# schematic.net
KiCad netlist of a schematic drawn in EAGLE
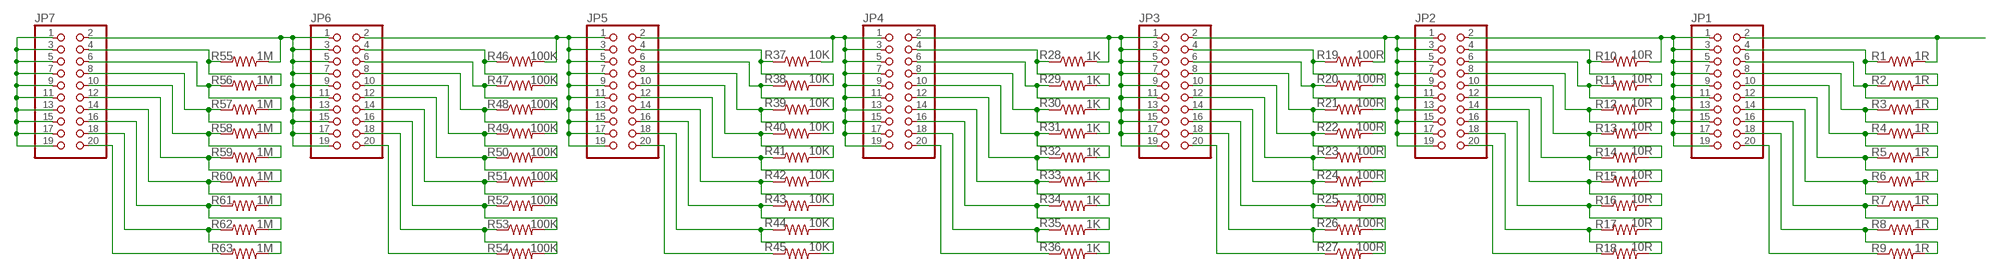
[diagram p0: schematic, sheet 1]

(export (version "E")
  (design (tool "Eeschema 10.0.6"))
  (components
    (comp (ref "JP1")
      (value "PINHD-2X10_2.54-SMD")
      (footprint "eagle-import:2X10SMD")
      (libsource (lib "eagle-import") (part "PINHD-2X10_2.54-SMD"))
    )
    (comp (ref "JP2")
      (value "PINHD-2X10_2.54-SMD")
      (footprint "eagle-import:2X10SMD")
      (libsource (lib "eagle-import") (part "PINHD-2X10_2.54-SMD"))
    )
    (comp (ref "JP3")
      (value "PINHD-2X10_2.54-SMD")
      (footprint "eagle-import:2X10SMD")
      (libsource (lib "eagle-import") (part "PINHD-2X10_2.54-SMD"))
    )
    (comp (ref "JP4")
      (value "PINHD-2X10_2.54-SMD")
      (footprint "eagle-import:2X10SMD")
      (libsource (lib "eagle-import") (part "PINHD-2X10_2.54-SMD"))
    )
    (comp (ref "JP5")
      (value "PINHD-2X10_2.54-SMD")
      (footprint "eagle-import:2X10SMD")
      (libsource (lib "eagle-import") (part "PINHD-2X10_2.54-SMD"))
    )
    (comp (ref "JP6")
      (value "PINHD-2X10_2.54-SMD")
      (footprint "eagle-import:2X10SMD")
      (libsource (lib "eagle-import") (part "PINHD-2X10_2.54-SMD"))
    )
    (comp (ref "JP7")
      (value "PINHD-2X10_2.54-SMD")
      (footprint "eagle-import:2X10SMD")
      (libsource (lib "eagle-import") (part "PINHD-2X10_2.54-SMD"))
    )
    (comp (ref "R1")
      (value "1R")
      (footprint "eagle-import:1206")
      (libsource (lib "eagle-import") (part "RESISTOR1206"))
    )
    (comp (ref "R2")
      (value "1R")
      (footprint "eagle-import:1206")
      (libsource (lib "eagle-import") (part "RESISTOR1206"))
    )
    (comp (ref "R3")
      (value "1R")
      (footprint "eagle-import:1206")
      (libsource (lib "eagle-import") (part "RESISTOR1206"))
    )
    (comp (ref "R4")
      (value "1R")
      (footprint "eagle-import:1206")
      (libsource (lib "eagle-import") (part "RESISTOR1206"))
    )
    (comp (ref "R5")
      (value "1R")
      (footprint "eagle-import:1206")
      (libsource (lib "eagle-import") (part "RESISTOR1206"))
    )
    (comp (ref "R6")
      (value "1R")
      (footprint "eagle-import:1206")
      (libsource (lib "eagle-import") (part "RESISTOR1206"))
    )
    (comp (ref "R7")
      (value "1R")
      (footprint "eagle-import:1206")
      (libsource (lib "eagle-import") (part "RESISTOR1206"))
    )
    (comp (ref "R8")
      (value "1R")
      (footprint "eagle-import:1206")
      (libsource (lib "eagle-import") (part "RESISTOR1206"))
    )
    (comp (ref "R9")
      (value "1R")
      (footprint "eagle-import:1206")
      (libsource (lib "eagle-import") (part "RESISTOR1206"))
    )
    (comp (ref "R10")
      (value "10R")
      (footprint "eagle-import:R2512")
      (libsource (lib "eagle-import") (part "RESISTOR2512"))
    )
    (comp (ref "R11")
      (value "10R")
      (footprint "eagle-import:R2512")
      (libsource (lib "eagle-import") (part "RESISTOR2512"))
    )
    (comp (ref "R12")
      (value "10R")
      (footprint "eagle-import:R2512")
      (libsource (lib "eagle-import") (part "RESISTOR2512"))
    )
    (comp (ref "R13")
      (value "10R")
      (footprint "eagle-import:R2512")
      (libsource (lib "eagle-import") (part "RESISTOR2512"))
    )
    (comp (ref "R14")
      (value "10R")
      (footprint "eagle-import:R2512")
      (libsource (lib "eagle-import") (part "RESISTOR2512"))
    )
    (comp (ref "R15")
      (value "10R")
      (footprint "eagle-import:R2512")
      (libsource (lib "eagle-import") (part "RESISTOR2512"))
    )
    (comp (ref "R16")
      (value "10R")
      (footprint "eagle-import:R2512")
      (libsource (lib "eagle-import") (part "RESISTOR2512"))
    )
    (comp (ref "R17")
      (value "10R")
      (footprint "eagle-import:R2512")
      (libsource (lib "eagle-import") (part "RESISTOR2512"))
    )
    (comp (ref "R18")
      (value "10R")
      (footprint "eagle-import:R2512")
      (libsource (lib "eagle-import") (part "RESISTOR2512"))
    )
    (comp (ref "R19")
      (value "100R")
      (footprint "eagle-import:R2512")
      (libsource (lib "eagle-import") (part "RESISTOR2512"))
    )
    (comp (ref "R20")
      (value "100R")
      (footprint "eagle-import:R2512")
      (libsource (lib "eagle-import") (part "RESISTOR2512"))
    )
    (comp (ref "R21")
      (value "100R")
      (footprint "eagle-import:R2512")
      (libsource (lib "eagle-import") (part "RESISTOR2512"))
    )
    (comp (ref "R22")
      (value "100R")
      (footprint "eagle-import:R2512")
      (libsource (lib "eagle-import") (part "RESISTOR2512"))
    )
    (comp (ref "R23")
      (value "100R")
      (footprint "eagle-import:R2512")
      (libsource (lib "eagle-import") (part "RESISTOR2512"))
    )
    (comp (ref "R24")
      (value "100R")
      (footprint "eagle-import:R2512")
      (libsource (lib "eagle-import") (part "RESISTOR2512"))
    )
    (comp (ref "R25")
      (value "100R")
      (footprint "eagle-import:R2512")
      (libsource (lib "eagle-import") (part "RESISTOR2512"))
    )
    (comp (ref "R26")
      (value "100R")
      (footprint "eagle-import:R2512")
      (libsource (lib "eagle-import") (part "RESISTOR2512"))
    )
    (comp (ref "R27")
      (value "100R")
      (footprint "eagle-import:R2512")
      (libsource (lib "eagle-import") (part "RESISTOR2512"))
    )
    (comp (ref "R28")
      (value "1K")
      (footprint "eagle-import:R2512")
      (libsource (lib "eagle-import") (part "RESISTOR2512"))
    )
    (comp (ref "R29")
      (value "1K")
      (footprint "eagle-import:R2512")
      (libsource (lib "eagle-import") (part "RESISTOR2512"))
    )
    (comp (ref "R30")
      (value "1K")
      (footprint "eagle-import:R2512")
      (libsource (lib "eagle-import") (part "RESISTOR2512"))
    )
    (comp (ref "R31")
      (value "1K")
      (footprint "eagle-import:R2512")
      (libsource (lib "eagle-import") (part "RESISTOR2512"))
    )
    (comp (ref "R32")
      (value "1K")
      (footprint "eagle-import:R2512")
      (libsource (lib "eagle-import") (part "RESISTOR2512"))
    )
    (comp (ref "R33")
      (value "1K")
      (footprint "eagle-import:R2512")
      (libsource (lib "eagle-import") (part "RESISTOR2512"))
    )
    (comp (ref "R34")
      (value "1K")
      (footprint "eagle-import:R2512")
      (libsource (lib "eagle-import") (part "RESISTOR2512"))
    )
    (comp (ref "R35")
      (value "1K")
      (footprint "eagle-import:R2512")
      (libsource (lib "eagle-import") (part "RESISTOR2512"))
    )
    (comp (ref "R36")
      (value "1K")
      (footprint "eagle-import:R2512")
      (libsource (lib "eagle-import") (part "RESISTOR2512"))
    )
    (comp (ref "R37")
      (value "10K")
      (footprint "eagle-import:R2512")
      (libsource (lib "eagle-import") (part "RESISTOR2512"))
    )
    (comp (ref "R38")
      (value "10K")
      (footprint "eagle-import:R2512")
      (libsource (lib "eagle-import") (part "RESISTOR2512"))
    )
    (comp (ref "R39")
      (value "10K")
      (footprint "eagle-import:R2512")
      (libsource (lib "eagle-import") (part "RESISTOR2512"))
    )
    (comp (ref "R40")
      (value "10K")
      (footprint "eagle-import:R2512")
      (libsource (lib "eagle-import") (part "RESISTOR2512"))
    )
    (comp (ref "R41")
      (value "10K")
      (footprint "eagle-import:R2512")
      (libsource (lib "eagle-import") (part "RESISTOR2512"))
    )
    (comp (ref "R42")
      (value "10K")
      (footprint "eagle-import:R2512")
      (libsource (lib "eagle-import") (part "RESISTOR2512"))
    )
    (comp (ref "R43")
      (value "10K")
      (footprint "eagle-import:R2512")
      (libsource (lib "eagle-import") (part "RESISTOR2512"))
    )
    (comp (ref "R44")
      (value "10K")
      (footprint "eagle-import:R2512")
      (libsource (lib "eagle-import") (part "RESISTOR2512"))
    )
    (comp (ref "R45")
      (value "10K")
      (footprint "eagle-import:R2512")
      (libsource (lib "eagle-import") (part "RESISTOR2512"))
    )
    (comp (ref "R46")
      (value "100K")
      (footprint "eagle-import:R2512")
      (libsource (lib "eagle-import") (part "RESISTOR2512"))
    )
    (comp (ref "R47")
      (value "100K")
      (footprint "eagle-import:R2512")
      (libsource (lib "eagle-import") (part "RESISTOR2512"))
    )
    (comp (ref "R48")
      (value "100K")
      (footprint "eagle-import:R2512")
      (libsource (lib "eagle-import") (part "RESISTOR2512"))
    )
    (comp (ref "R49")
      (value "100K")
      (footprint "eagle-import:R2512")
      (libsource (lib "eagle-import") (part "RESISTOR2512"))
    )
    (comp (ref "R50")
      (value "100K")
      (footprint "eagle-import:R2512")
      (libsource (lib "eagle-import") (part "RESISTOR2512"))
    )
    (comp (ref "R51")
      (value "100K")
      (footprint "eagle-import:R2512")
      (libsource (lib "eagle-import") (part "RESISTOR2512"))
    )
    (comp (ref "R52")
      (value "100K")
      (footprint "eagle-import:R2512")
      (libsource (lib "eagle-import") (part "RESISTOR2512"))
    )
    (comp (ref "R53")
      (value "100K")
      (footprint "eagle-import:R2512")
      (libsource (lib "eagle-import") (part "RESISTOR2512"))
    )
    (comp (ref "R54")
      (value "100K")
      (footprint "eagle-import:R2512")
      (libsource (lib "eagle-import") (part "RESISTOR2512"))
    )
    (comp (ref "R55")
      (value "1M")
      (footprint "eagle-import:R2512")
      (libsource (lib "eagle-import") (part "RESISTOR2512"))
    )
    (comp (ref "R56")
      (value "1M")
      (footprint "eagle-import:R2512")
      (libsource (lib "eagle-import") (part "RESISTOR2512"))
    )
    (comp (ref "R57")
      (value "1M")
      (footprint "eagle-import:R2512")
      (libsource (lib "eagle-import") (part "RESISTOR2512"))
    )
    (comp (ref "R58")
      (value "1M")
      (footprint "eagle-import:R2512")
      (libsource (lib "eagle-import") (part "RESISTOR2512"))
    )
    (comp (ref "R59")
      (value "1M")
      (footprint "eagle-import:R2512")
      (libsource (lib "eagle-import") (part "RESISTOR2512"))
    )
    (comp (ref "R60")
      (value "1M")
      (footprint "eagle-import:R2512")
      (libsource (lib "eagle-import") (part "RESISTOR2512"))
    )
    (comp (ref "R61")
      (value "1M")
      (footprint "eagle-import:R2512")
      (libsource (lib "eagle-import") (part "RESISTOR2512"))
    )
    (comp (ref "R62")
      (value "1M")
      (footprint "eagle-import:R2512")
      (libsource (lib "eagle-import") (part "RESISTOR2512"))
    )
    (comp (ref "R63")
      (value "1M")
      (footprint "eagle-import:R2512")
      (libsource (lib "eagle-import") (part "RESISTOR2512"))
    )
  )
  (nets
    (net (code "1") (name "Net-(JP1-Pad1)") (class "Default")
      (node (ref "JP1") (pin "1") (pinfunction "1_1") (pintype "passive"))
      (node (ref "JP1") (pin "11") (pinfunction "11_11") (pintype "passive"))
      (node (ref "JP1") (pin "13") (pinfunction "13_13") (pintype "passive"))
      (node (ref "JP1") (pin "15") (pinfunction "15_15") (pintype "passive"))
      (node (ref "JP1") (pin "17") (pinfunction "17_17") (pintype "passive"))
      (node (ref "JP1") (pin "19") (pinfunction "19_19") (pintype "passive"))
      (node (ref "JP1") (pin "3") (pinfunction "3_3") (pintype "passive"))
      (node (ref "JP1") (pin "5") (pinfunction "5_5") (pintype "passive"))
      (node (ref "JP1") (pin "7") (pinfunction "7_7") (pintype "passive"))
      (node (ref "JP1") (pin "9") (pinfunction "9_9") (pintype "passive"))
      (node (ref "JP2") (pin "2") (pinfunction "2_2") (pintype "passive"))
      (node (ref "R10") (pin "2") (pinfunction "2_2") (pintype "passive"))
    )
    (net (code "2") (name "Net-(JP1-Pad2)") (class "Default")
      (node (ref "JP1") (pin "2") (pinfunction "2_2") (pintype "passive"))
      (node (ref "R1") (pin "2") (pinfunction "2_2") (pintype "passive"))
    )
    (net (code "3") (name "Net-(JP1-Pad4)") (class "Default")
      (node (ref "JP1") (pin "4") (pinfunction "4_4") (pintype "passive"))
      (node (ref "R1") (pin "1") (pinfunction "1_1") (pintype "passive"))
      (node (ref "R2") (pin "2") (pinfunction "2_2") (pintype "passive"))
    )
    (net (code "4") (name "Net-(JP1-Pad6)") (class "Default")
      (node (ref "JP1") (pin "6") (pinfunction "6_6") (pintype "passive"))
      (node (ref "R2") (pin "1") (pinfunction "1_1") (pintype "passive"))
      (node (ref "R3") (pin "2") (pinfunction "2_2") (pintype "passive"))
    )
    (net (code "5") (name "Net-(JP1-Pad8)") (class "Default")
      (node (ref "JP1") (pin "8") (pinfunction "8_8") (pintype "passive"))
      (node (ref "R3") (pin "1") (pinfunction "1_1") (pintype "passive"))
      (node (ref "R4") (pin "2") (pinfunction "2_2") (pintype "passive"))
    )
    (net (code "6") (name "Net-(JP1-Pad10)") (class "Default")
      (node (ref "JP1") (pin "10") (pinfunction "10_10") (pintype "passive"))
      (node (ref "R4") (pin "1") (pinfunction "1_1") (pintype "passive"))
      (node (ref "R5") (pin "2") (pinfunction "2_2") (pintype "passive"))
    )
    (net (code "7") (name "Net-(JP1-Pad12)") (class "Default")
      (node (ref "JP1") (pin "12") (pinfunction "12_12") (pintype "passive"))
      (node (ref "R5") (pin "1") (pinfunction "1_1") (pintype "passive"))
      (node (ref "R6") (pin "2") (pinfunction "2_2") (pintype "passive"))
    )
    (net (code "8") (name "Net-(JP1-Pad14)") (class "Default")
      (node (ref "JP1") (pin "14") (pinfunction "14_14") (pintype "passive"))
      (node (ref "R6") (pin "1") (pinfunction "1_1") (pintype "passive"))
      (node (ref "R7") (pin "2") (pinfunction "2_2") (pintype "passive"))
    )
    (net (code "9") (name "Net-(JP1-Pad16)") (class "Default")
      (node (ref "JP1") (pin "16") (pinfunction "16_16") (pintype "passive"))
      (node (ref "R7") (pin "1") (pinfunction "1_1") (pintype "passive"))
      (node (ref "R8") (pin "2") (pinfunction "2_2") (pintype "passive"))
    )
    (net (code "10") (name "Net-(JP1-Pad18)") (class "Default")
      (node (ref "JP1") (pin "18") (pinfunction "18_18") (pintype "passive"))
      (node (ref "R8") (pin "1") (pinfunction "1_1") (pintype "passive"))
      (node (ref "R9") (pin "2") (pinfunction "2_2") (pintype "passive"))
    )
    (net (code "11") (name "Net-(JP1-Pad20)") (class "Default")
      (node (ref "JP1") (pin "20") (pinfunction "20_20") (pintype "passive"))
      (node (ref "R9") (pin "1") (pinfunction "1_1") (pintype "passive"))
    )
    (net (code "12") (name "Net-(JP2-Pad1)") (class "Default")
      (node (ref "JP2") (pin "1") (pinfunction "1_1") (pintype "passive"))
      (node (ref "JP2") (pin "11") (pinfunction "11_11") (pintype "passive"))
      (node (ref "JP2") (pin "13") (pinfunction "13_13") (pintype "passive"))
      (node (ref "JP2") (pin "15") (pinfunction "15_15") (pintype "passive"))
      (node (ref "JP2") (pin "17") (pinfunction "17_17") (pintype "passive"))
      (node (ref "JP2") (pin "19") (pinfunction "19_19") (pintype "passive"))
      (node (ref "JP2") (pin "3") (pinfunction "3_3") (pintype "passive"))
      (node (ref "JP2") (pin "5") (pinfunction "5_5") (pintype "passive"))
      (node (ref "JP2") (pin "7") (pinfunction "7_7") (pintype "passive"))
      (node (ref "JP2") (pin "9") (pinfunction "9_9") (pintype "passive"))
      (node (ref "JP3") (pin "2") (pinfunction "2_2") (pintype "passive"))
      (node (ref "R19") (pin "2") (pinfunction "2_2") (pintype "passive"))
    )
    (net (code "13") (name "Net-(JP2-Pad4)") (class "Default")
      (node (ref "JP2") (pin "4") (pinfunction "4_4") (pintype "passive"))
      (node (ref "R10") (pin "1") (pinfunction "1_1") (pintype "passive"))
      (node (ref "R11") (pin "2") (pinfunction "2_2") (pintype "passive"))
    )
    (net (code "14") (name "Net-(JP2-Pad6)") (class "Default")
      (node (ref "JP2") (pin "6") (pinfunction "6_6") (pintype "passive"))
      (node (ref "R11") (pin "1") (pinfunction "1_1") (pintype "passive"))
      (node (ref "R12") (pin "2") (pinfunction "2_2") (pintype "passive"))
    )
    (net (code "15") (name "Net-(JP2-Pad8)") (class "Default")
      (node (ref "JP2") (pin "8") (pinfunction "8_8") (pintype "passive"))
      (node (ref "R12") (pin "1") (pinfunction "1_1") (pintype "passive"))
      (node (ref "R13") (pin "2") (pinfunction "2_2") (pintype "passive"))
    )
    (net (code "16") (name "Net-(JP2-Pad10)") (class "Default")
      (node (ref "JP2") (pin "10") (pinfunction "10_10") (pintype "passive"))
      (node (ref "R13") (pin "1") (pinfunction "1_1") (pintype "passive"))
      (node (ref "R14") (pin "2") (pinfunction "2_2") (pintype "passive"))
    )
    (net (code "17") (name "Net-(JP2-Pad12)") (class "Default")
      (node (ref "JP2") (pin "12") (pinfunction "12_12") (pintype "passive"))
      (node (ref "R14") (pin "1") (pinfunction "1_1") (pintype "passive"))
      (node (ref "R15") (pin "2") (pinfunction "2_2") (pintype "passive"))
    )
    (net (code "18") (name "Net-(JP2-Pad14)") (class "Default")
      (node (ref "JP2") (pin "14") (pinfunction "14_14") (pintype "passive"))
      (node (ref "R15") (pin "1") (pinfunction "1_1") (pintype "passive"))
      (node (ref "R16") (pin "2") (pinfunction "2_2") (pintype "passive"))
    )
    (net (code "19") (name "Net-(JP2-Pad16)") (class "Default")
      (node (ref "JP2") (pin "16") (pinfunction "16_16") (pintype "passive"))
      (node (ref "R16") (pin "1") (pinfunction "1_1") (pintype "passive"))
      (node (ref "R17") (pin "2") (pinfunction "2_2") (pintype "passive"))
    )
    (net (code "20") (name "Net-(JP2-Pad18)") (class "Default")
      (node (ref "JP2") (pin "18") (pinfunction "18_18") (pintype "passive"))
      (node (ref "R17") (pin "1") (pinfunction "1_1") (pintype "passive"))
      (node (ref "R18") (pin "2") (pinfunction "2_2") (pintype "passive"))
    )
    (net (code "21") (name "Net-(JP2-Pad20)") (class "Default")
      (node (ref "JP2") (pin "20") (pinfunction "20_20") (pintype "passive"))
      (node (ref "R18") (pin "1") (pinfunction "1_1") (pintype "passive"))
    )
    (net (code "22") (name "Net-(JP3-Pad1)") (class "Default")
      (node (ref "JP3") (pin "1") (pinfunction "1_1") (pintype "passive"))
      (node (ref "JP3") (pin "11") (pinfunction "11_11") (pintype "passive"))
      (node (ref "JP3") (pin "13") (pinfunction "13_13") (pintype "passive"))
      (node (ref "JP3") (pin "15") (pinfunction "15_15") (pintype "passive"))
      (node (ref "JP3") (pin "17") (pinfunction "17_17") (pintype "passive"))
      (node (ref "JP3") (pin "19") (pinfunction "19_19") (pintype "passive"))
      (node (ref "JP3") (pin "3") (pinfunction "3_3") (pintype "passive"))
      (node (ref "JP3") (pin "5") (pinfunction "5_5") (pintype "passive"))
      (node (ref "JP3") (pin "7") (pinfunction "7_7") (pintype "passive"))
      (node (ref "JP3") (pin "9") (pinfunction "9_9") (pintype "passive"))
      (node (ref "JP4") (pin "2") (pinfunction "2_2") (pintype "passive"))
      (node (ref "R28") (pin "2") (pinfunction "2_2") (pintype "passive"))
    )
    (net (code "23") (name "Net-(JP3-Pad4)") (class "Default")
      (node (ref "JP3") (pin "4") (pinfunction "4_4") (pintype "passive"))
      (node (ref "R19") (pin "1") (pinfunction "1_1") (pintype "passive"))
      (node (ref "R20") (pin "2") (pinfunction "2_2") (pintype "passive"))
    )
    (net (code "24") (name "Net-(JP3-Pad6)") (class "Default")
      (node (ref "JP3") (pin "6") (pinfunction "6_6") (pintype "passive"))
      (node (ref "R20") (pin "1") (pinfunction "1_1") (pintype "passive"))
      (node (ref "R21") (pin "2") (pinfunction "2_2") (pintype "passive"))
    )
    (net (code "25") (name "Net-(JP3-Pad8)") (class "Default")
      (node (ref "JP3") (pin "8") (pinfunction "8_8") (pintype "passive"))
      (node (ref "R21") (pin "1") (pinfunction "1_1") (pintype "passive"))
      (node (ref "R22") (pin "2") (pinfunction "2_2") (pintype "passive"))
    )
    (net (code "26") (name "Net-(JP3-Pad10)") (class "Default")
      (node (ref "JP3") (pin "10") (pinfunction "10_10") (pintype "passive"))
      (node (ref "R22") (pin "1") (pinfunction "1_1") (pintype "passive"))
      (node (ref "R23") (pin "2") (pinfunction "2_2") (pintype "passive"))
    )
    (net (code "27") (name "Net-(JP3-Pad12)") (class "Default")
      (node (ref "JP3") (pin "12") (pinfunction "12_12") (pintype "passive"))
      (node (ref "R23") (pin "1") (pinfunction "1_1") (pintype "passive"))
      (node (ref "R24") (pin "2") (pinfunction "2_2") (pintype "passive"))
    )
    (net (code "28") (name "Net-(JP3-Pad14)") (class "Default")
      (node (ref "JP3") (pin "14") (pinfunction "14_14") (pintype "passive"))
      (node (ref "R24") (pin "1") (pinfunction "1_1") (pintype "passive"))
      (node (ref "R25") (pin "2") (pinfunction "2_2") (pintype "passive"))
    )
    (net (code "29") (name "Net-(JP3-Pad16)") (class "Default")
      (node (ref "JP3") (pin "16") (pinfunction "16_16") (pintype "passive"))
      (node (ref "R25") (pin "1") (pinfunction "1_1") (pintype "passive"))
      (node (ref "R26") (pin "2") (pinfunction "2_2") (pintype "passive"))
    )
    (net (code "30") (name "Net-(JP3-Pad18)") (class "Default")
      (node (ref "JP3") (pin "18") (pinfunction "18_18") (pintype "passive"))
      (node (ref "R26") (pin "1") (pinfunction "1_1") (pintype "passive"))
      (node (ref "R27") (pin "2") (pinfunction "2_2") (pintype "passive"))
    )
    (net (code "31") (name "Net-(JP3-Pad20)") (class "Default")
      (node (ref "JP3") (pin "20") (pinfunction "20_20") (pintype "passive"))
      (node (ref "R27") (pin "1") (pinfunction "1_1") (pintype "passive"))
    )
    (net (code "32") (name "Net-(JP4-Pad1)") (class "Default")
      (node (ref "JP4") (pin "1") (pinfunction "1_1") (pintype "passive"))
      (node (ref "JP4") (pin "11") (pinfunction "11_11") (pintype "passive"))
      (node (ref "JP4") (pin "13") (pinfunction "13_13") (pintype "passive"))
      (node (ref "JP4") (pin "15") (pinfunction "15_15") (pintype "passive"))
      (node (ref "JP4") (pin "17") (pinfunction "17_17") (pintype "passive"))
      (node (ref "JP4") (pin "19") (pinfunction "19_19") (pintype "passive"))
      (node (ref "JP4") (pin "3") (pinfunction "3_3") (pintype "passive"))
      (node (ref "JP4") (pin "5") (pinfunction "5_5") (pintype "passive"))
      (node (ref "JP4") (pin "7") (pinfunction "7_7") (pintype "passive"))
      (node (ref "JP4") (pin "9") (pinfunction "9_9") (pintype "passive"))
      (node (ref "JP5") (pin "2") (pinfunction "2_2") (pintype "passive"))
      (node (ref "R37") (pin "2") (pinfunction "2_2") (pintype "passive"))
    )
    (net (code "33") (name "Net-(JP4-Pad4)") (class "Default")
      (node (ref "JP4") (pin "4") (pinfunction "4_4") (pintype "passive"))
      (node (ref "R28") (pin "1") (pinfunction "1_1") (pintype "passive"))
      (node (ref "R29") (pin "2") (pinfunction "2_2") (pintype "passive"))
    )
    (net (code "34") (name "Net-(JP4-Pad6)") (class "Default")
      (node (ref "JP4") (pin "6") (pinfunction "6_6") (pintype "passive"))
      (node (ref "R29") (pin "1") (pinfunction "1_1") (pintype "passive"))
      (node (ref "R30") (pin "2") (pinfunction "2_2") (pintype "passive"))
    )
    (net (code "35") (name "Net-(JP4-Pad8)") (class "Default")
      (node (ref "JP4") (pin "8") (pinfunction "8_8") (pintype "passive"))
      (node (ref "R30") (pin "1") (pinfunction "1_1") (pintype "passive"))
      (node (ref "R31") (pin "2") (pinfunction "2_2") (pintype "passive"))
    )
    (net (code "36") (name "Net-(JP4-Pad10)") (class "Default")
      (node (ref "JP4") (pin "10") (pinfunction "10_10") (pintype "passive"))
      (node (ref "R31") (pin "1") (pinfunction "1_1") (pintype "passive"))
      (node (ref "R32") (pin "2") (pinfunction "2_2") (pintype "passive"))
    )
    (net (code "37") (name "Net-(JP4-Pad12)") (class "Default")
      (node (ref "JP4") (pin "12") (pinfunction "12_12") (pintype "passive"))
      (node (ref "R32") (pin "1") (pinfunction "1_1") (pintype "passive"))
      (node (ref "R33") (pin "2") (pinfunction "2_2") (pintype "passive"))
    )
    (net (code "38") (name "Net-(JP4-Pad14)") (class "Default")
      (node (ref "JP4") (pin "14") (pinfunction "14_14") (pintype "passive"))
      (node (ref "R33") (pin "1") (pinfunction "1_1") (pintype "passive"))
      (node (ref "R34") (pin "2") (pinfunction "2_2") (pintype "passive"))
    )
    (net (code "39") (name "Net-(JP4-Pad16)") (class "Default")
      (node (ref "JP4") (pin "16") (pinfunction "16_16") (pintype "passive"))
      (node (ref "R34") (pin "1") (pinfunction "1_1") (pintype "passive"))
      (node (ref "R35") (pin "2") (pinfunction "2_2") (pintype "passive"))
    )
    (net (code "40") (name "Net-(JP4-Pad18)") (class "Default")
      (node (ref "JP4") (pin "18") (pinfunction "18_18") (pintype "passive"))
      (node (ref "R35") (pin "1") (pinfunction "1_1") (pintype "passive"))
      (node (ref "R36") (pin "2") (pinfunction "2_2") (pintype "passive"))
    )
    (net (code "41") (name "Net-(JP4-Pad20)") (class "Default")
      (node (ref "JP4") (pin "20") (pinfunction "20_20") (pintype "passive"))
      (node (ref "R36") (pin "1") (pinfunction "1_1") (pintype "passive"))
    )
    (net (code "42") (name "Net-(JP5-Pad1)") (class "Default")
      (node (ref "JP5") (pin "1") (pinfunction "1_1") (pintype "passive"))
      (node (ref "JP5") (pin "11") (pinfunction "11_11") (pintype "passive"))
      (node (ref "JP5") (pin "13") (pinfunction "13_13") (pintype "passive"))
      (node (ref "JP5") (pin "15") (pinfunction "15_15") (pintype "passive"))
      (node (ref "JP5") (pin "17") (pinfunction "17_17") (pintype "passive"))
      (node (ref "JP5") (pin "19") (pinfunction "19_19") (pintype "passive"))
      (node (ref "JP5") (pin "3") (pinfunction "3_3") (pintype "passive"))
      (node (ref "JP5") (pin "5") (pinfunction "5_5") (pintype "passive"))
      (node (ref "JP5") (pin "7") (pinfunction "7_7") (pintype "passive"))
      (node (ref "JP5") (pin "9") (pinfunction "9_9") (pintype "passive"))
      (node (ref "JP6") (pin "2") (pinfunction "2_2") (pintype "passive"))
      (node (ref "R46") (pin "2") (pinfunction "2_2") (pintype "passive"))
    )
    (net (code "43") (name "Net-(JP5-Pad4)") (class "Default")
      (node (ref "JP5") (pin "4") (pinfunction "4_4") (pintype "passive"))
      (node (ref "R37") (pin "1") (pinfunction "1_1") (pintype "passive"))
      (node (ref "R38") (pin "2") (pinfunction "2_2") (pintype "passive"))
    )
    (net (code "44") (name "Net-(JP5-Pad6)") (class "Default")
      (node (ref "JP5") (pin "6") (pinfunction "6_6") (pintype "passive"))
      (node (ref "R38") (pin "1") (pinfunction "1_1") (pintype "passive"))
      (node (ref "R39") (pin "2") (pinfunction "2_2") (pintype "passive"))
    )
    (net (code "45") (name "Net-(JP5-Pad8)") (class "Default")
      (node (ref "JP5") (pin "8") (pinfunction "8_8") (pintype "passive"))
      (node (ref "R39") (pin "1") (pinfunction "1_1") (pintype "passive"))
      (node (ref "R40") (pin "2") (pinfunction "2_2") (pintype "passive"))
    )
    (net (code "46") (name "Net-(JP5-Pad10)") (class "Default")
      (node (ref "JP5") (pin "10") (pinfunction "10_10") (pintype "passive"))
      (node (ref "R40") (pin "1") (pinfunction "1_1") (pintype "passive"))
      (node (ref "R41") (pin "2") (pinfunction "2_2") (pintype "passive"))
    )
    (net (code "47") (name "Net-(JP5-Pad12)") (class "Default")
      (node (ref "JP5") (pin "12") (pinfunction "12_12") (pintype "passive"))
      (node (ref "R41") (pin "1") (pinfunction "1_1") (pintype "passive"))
      (node (ref "R42") (pin "2") (pinfunction "2_2") (pintype "passive"))
    )
    (net (code "48") (name "Net-(JP5-Pad14)") (class "Default")
      (node (ref "JP5") (pin "14") (pinfunction "14_14") (pintype "passive"))
      (node (ref "R42") (pin "1") (pinfunction "1_1") (pintype "passive"))
      (node (ref "R43") (pin "2") (pinfunction "2_2") (pintype "passive"))
    )
    (net (code "49") (name "Net-(JP5-Pad16)") (class "Default")
      (node (ref "JP5") (pin "16") (pinfunction "16_16") (pintype "passive"))
      (node (ref "R43") (pin "1") (pinfunction "1_1") (pintype "passive"))
      (node (ref "R44") (pin "2") (pinfunction "2_2") (pintype "passive"))
    )
    (net (code "50") (name "Net-(JP5-Pad18)") (class "Default")
      (node (ref "JP5") (pin "18") (pinfunction "18_18") (pintype "passive"))
      (node (ref "R44") (pin "1") (pinfunction "1_1") (pintype "passive"))
      (node (ref "R45") (pin "2") (pinfunction "2_2") (pintype "passive"))
    )
    (net (code "51") (name "Net-(JP5-Pad20)") (class "Default")
      (node (ref "JP5") (pin "20") (pinfunction "20_20") (pintype "passive"))
      (node (ref "R45") (pin "1") (pinfunction "1_1") (pintype "passive"))
    )
    (net (code "52") (name "Net-(JP6-Pad1)") (class "Default")
      (node (ref "JP6") (pin "1") (pinfunction "1_1") (pintype "passive"))
      (node (ref "JP6") (pin "11") (pinfunction "11_11") (pintype "passive"))
      (node (ref "JP6") (pin "13") (pinfunction "13_13") (pintype "passive"))
      (node (ref "JP6") (pin "15") (pinfunction "15_15") (pintype "passive"))
      (node (ref "JP6") (pin "17") (pinfunction "17_17") (pintype "passive"))
      (node (ref "JP6") (pin "19") (pinfunction "19_19") (pintype "passive"))
      (node (ref "JP6") (pin "3") (pinfunction "3_3") (pintype "passive"))
      (node (ref "JP6") (pin "5") (pinfunction "5_5") (pintype "passive"))
      (node (ref "JP6") (pin "7") (pinfunction "7_7") (pintype "passive"))
      (node (ref "JP6") (pin "9") (pinfunction "9_9") (pintype "passive"))
      (node (ref "JP7") (pin "2") (pinfunction "2_2") (pintype "passive"))
      (node (ref "R55") (pin "2") (pinfunction "2_2") (pintype "passive"))
    )
    (net (code "53") (name "Net-(JP6-Pad4)") (class "Default")
      (node (ref "JP6") (pin "4") (pinfunction "4_4") (pintype "passive"))
      (node (ref "R46") (pin "1") (pinfunction "1_1") (pintype "passive"))
      (node (ref "R47") (pin "2") (pinfunction "2_2") (pintype "passive"))
    )
    (net (code "54") (name "Net-(JP6-Pad6)") (class "Default")
      (node (ref "JP6") (pin "6") (pinfunction "6_6") (pintype "passive"))
      (node (ref "R47") (pin "1") (pinfunction "1_1") (pintype "passive"))
      (node (ref "R48") (pin "2") (pinfunction "2_2") (pintype "passive"))
    )
    (net (code "55") (name "Net-(JP6-Pad8)") (class "Default")
      (node (ref "JP6") (pin "8") (pinfunction "8_8") (pintype "passive"))
      (node (ref "R48") (pin "1") (pinfunction "1_1") (pintype "passive"))
      (node (ref "R49") (pin "2") (pinfunction "2_2") (pintype "passive"))
    )
    (net (code "56") (name "Net-(JP6-Pad10)") (class "Default")
      (node (ref "JP6") (pin "10") (pinfunction "10_10") (pintype "passive"))
      (node (ref "R49") (pin "1") (pinfunction "1_1") (pintype "passive"))
      (node (ref "R50") (pin "2") (pinfunction "2_2") (pintype "passive"))
    )
    (net (code "57") (name "Net-(JP6-Pad12)") (class "Default")
      (node (ref "JP6") (pin "12") (pinfunction "12_12") (pintype "passive"))
      (node (ref "R50") (pin "1") (pinfunction "1_1") (pintype "passive"))
      (node (ref "R51") (pin "2") (pinfunction "2_2") (pintype "passive"))
    )
    (net (code "58") (name "Net-(JP6-Pad14)") (class "Default")
      (node (ref "JP6") (pin "14") (pinfunction "14_14") (pintype "passive"))
      (node (ref "R51") (pin "1") (pinfunction "1_1") (pintype "passive"))
      (node (ref "R52") (pin "2") (pinfunction "2_2") (pintype "passive"))
    )
    (net (code "59") (name "Net-(JP6-Pad16)") (class "Default")
      (node (ref "JP6") (pin "16") (pinfunction "16_16") (pintype "passive"))
      (node (ref "R52") (pin "1") (pinfunction "1_1") (pintype "passive"))
      (node (ref "R53") (pin "2") (pinfunction "2_2") (pintype "passive"))
    )
    (net (code "60") (name "Net-(JP6-Pad18)") (class "Default")
      (node (ref "JP6") (pin "18") (pinfunction "18_18") (pintype "passive"))
      (node (ref "R53") (pin "1") (pinfunction "1_1") (pintype "passive"))
      (node (ref "R54") (pin "2") (pinfunction "2_2") (pintype "passive"))
    )
    (net (code "61") (name "Net-(JP6-Pad20)") (class "Default")
      (node (ref "JP6") (pin "20") (pinfunction "20_20") (pintype "passive"))
      (node (ref "R54") (pin "1") (pinfunction "1_1") (pintype "passive"))
    )
    (net (code "62") (name "Net-(JP7-Pad1)") (class "Default")
      (node (ref "JP7") (pin "1") (pinfunction "1_1") (pintype "passive"))
      (node (ref "JP7") (pin "11") (pinfunction "11_11") (pintype "passive"))
      (node (ref "JP7") (pin "13") (pinfunction "13_13") (pintype "passive"))
      (node (ref "JP7") (pin "15") (pinfunction "15_15") (pintype "passive"))
      (node (ref "JP7") (pin "17") (pinfunction "17_17") (pintype "passive"))
      (node (ref "JP7") (pin "19") (pinfunction "19_19") (pintype "passive"))
      (node (ref "JP7") (pin "3") (pinfunction "3_3") (pintype "passive"))
      (node (ref "JP7") (pin "5") (pinfunction "5_5") (pintype "passive"))
      (node (ref "JP7") (pin "7") (pinfunction "7_7") (pintype "passive"))
      (node (ref "JP7") (pin "9") (pinfunction "9_9") (pintype "passive"))
    )
    (net (code "63") (name "Net-(JP7-Pad4)") (class "Default")
      (node (ref "JP7") (pin "4") (pinfunction "4_4") (pintype "passive"))
      (node (ref "R55") (pin "1") (pinfunction "1_1") (pintype "passive"))
      (node (ref "R56") (pin "2") (pinfunction "2_2") (pintype "passive"))
    )
    (net (code "64") (name "Net-(JP7-Pad6)") (class "Default")
      (node (ref "JP7") (pin "6") (pinfunction "6_6") (pintype "passive"))
      (node (ref "R56") (pin "1") (pinfunction "1_1") (pintype "passive"))
      (node (ref "R57") (pin "2") (pinfunction "2_2") (pintype "passive"))
    )
    (net (code "65") (name "Net-(JP7-Pad8)") (class "Default")
      (node (ref "JP7") (pin "8") (pinfunction "8_8") (pintype "passive"))
      (node (ref "R57") (pin "1") (pinfunction "1_1") (pintype "passive"))
      (node (ref "R58") (pin "2") (pinfunction "2_2") (pintype "passive"))
    )
    (net (code "66") (name "Net-(JP7-Pad10)") (class "Default")
      (node (ref "JP7") (pin "10") (pinfunction "10_10") (pintype "passive"))
      (node (ref "R58") (pin "1") (pinfunction "1_1") (pintype "passive"))
      (node (ref "R59") (pin "2") (pinfunction "2_2") (pintype "passive"))
    )
    (net (code "67") (name "Net-(JP7-Pad12)") (class "Default")
      (node (ref "JP7") (pin "12") (pinfunction "12_12") (pintype "passive"))
      (node (ref "R59") (pin "1") (pinfunction "1_1") (pintype "passive"))
      (node (ref "R60") (pin "2") (pinfunction "2_2") (pintype "passive"))
    )
    (net (code "68") (name "Net-(JP7-Pad14)") (class "Default")
      (node (ref "JP7") (pin "14") (pinfunction "14_14") (pintype "passive"))
      (node (ref "R60") (pin "1") (pinfunction "1_1") (pintype "passive"))
      (node (ref "R61") (pin "2") (pinfunction "2_2") (pintype "passive"))
    )
    (net (code "69") (name "Net-(JP7-Pad16)") (class "Default")
      (node (ref "JP7") (pin "16") (pinfunction "16_16") (pintype "passive"))
      (node (ref "R61") (pin "1") (pinfunction "1_1") (pintype "passive"))
      (node (ref "R62") (pin "2") (pinfunction "2_2") (pintype "passive"))
    )
    (net (code "70") (name "Net-(JP7-Pad18)") (class "Default")
      (node (ref "JP7") (pin "18") (pinfunction "18_18") (pintype "passive"))
      (node (ref "R62") (pin "1") (pinfunction "1_1") (pintype "passive"))
      (node (ref "R63") (pin "2") (pinfunction "2_2") (pintype "passive"))
    )
    (net (code "71") (name "Net-(JP7-Pad20)") (class "Default")
      (node (ref "JP7") (pin "20") (pinfunction "20_20") (pintype "passive"))
      (node (ref "R63") (pin "1") (pinfunction "1_1") (pintype "passive"))
    )
  )
)
